# MRCS-Don-Wood-IR-Detector-Circuit.net
KiCad netlist of a schematic drawn in EAGLE
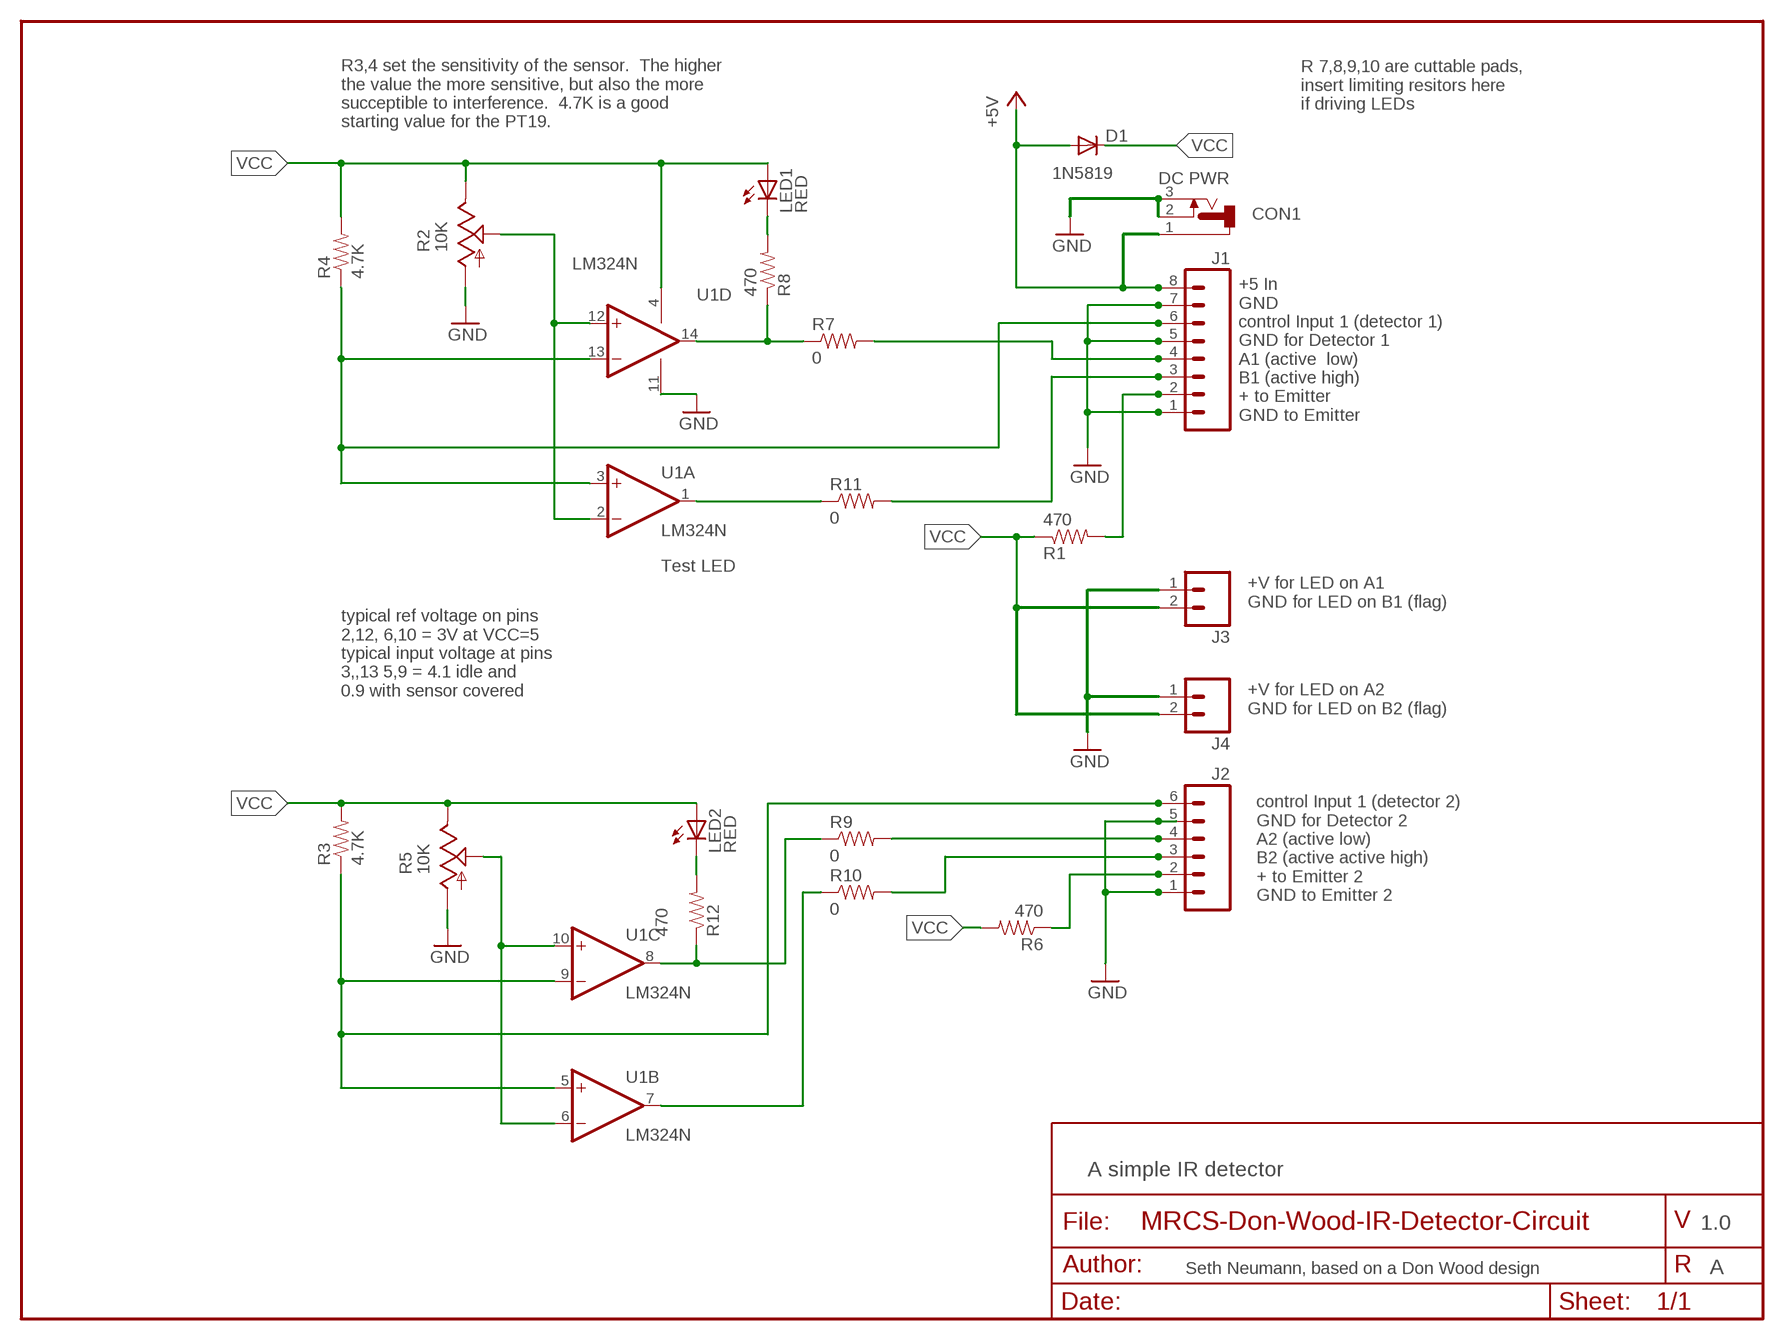
[diagram p0: schematic, sheet 1]

(export (version "E")
  (design (tool "Eeschema 10.0.6"))
  (components
    (comp (ref "CON1")
      (value "DC PWR")
      (footprint "eagle-import:DCJ0202")
      (libsource (lib "eagle-import") (part "CONNECTOR-DC-POWER-RA"))
    )
    (comp (ref "D1")
      (value "1N5819")
      (footprint "eagle-import:DIODE-1N4001")
      (libsource (lib "eagle-import") (part "DIODEPTH"))
    )
    (comp (ref "J1")
      (value "CONNECTOR-M08LOCK")
      (footprint "eagle-import:1X08_LOCK")
      (libsource (lib "eagle-import") (part "CONNECTOR-M08LOCK"))
    )
    (comp (ref "J2")
      (value "CONNECTOR-M06LOCK")
      (footprint "eagle-import:1X06_LOCK")
      (libsource (lib "eagle-import") (part "CONNECTOR-M06LOCK"))
    )
    (comp (ref "J3")
      (value "CONNECTOR-M021X02-LOCK")
      (footprint "eagle-import:1X02_LOCK")
      (libsource (lib "eagle-import") (part "CONNECTOR-M021X02-LOCK"))
    )
    (comp (ref "J4")
      (value "CONNECTOR-M021X02-LOCK")
      (footprint "eagle-import:1X02_LOCK")
      (libsource (lib "eagle-import") (part "CONNECTOR-M021X02-LOCK"))
    )
    (comp (ref "LED1")
      (value "RED")
      (footprint "eagle-import:LED3MM")
      (libsource (lib "eagle-import") (part "LEDLED3MM"))
    )
    (comp (ref "LED2")
      (value "RED")
      (footprint "eagle-import:LED3MM")
      (libsource (lib "eagle-import") (part "LEDLED3MM"))
    )
    (comp (ref "R1")
      (value "470")
      (footprint "eagle-import:AXIAL-0.4-RES")
      (libsource (lib "eagle-import") (part "RPTH04"))
    )
    (comp (ref "R2")
      (value "10K")
      (footprint "eagle-import:RS3")
      (libsource (lib "eagle-import") (part "TRIM_US-RS3"))
    )
    (comp (ref "R3")
      (value "4.7K")
      (footprint "eagle-import:AXIAL-0.4-RES")
      (libsource (lib "eagle-import") (part "RPTH04"))
    )
    (comp (ref "R4")
      (value "4.7K")
      (footprint "eagle-import:AXIAL-0.4-RES")
      (libsource (lib "eagle-import") (part "RPTH04"))
    )
    (comp (ref "R5")
      (value "10K")
      (footprint "eagle-import:RS3")
      (libsource (lib "eagle-import") (part "TRIM_US-RS3"))
    )
    (comp (ref "R6")
      (value "470")
      (footprint "eagle-import:AXIAL-0.4-RES")
      (libsource (lib "eagle-import") (part "RPTH04"))
    )
    (comp (ref "R7")
      (value "0")
      (footprint "eagle-import:CUT-R")
      (libsource (lib "eagle-import") (part "RPTH-R0"))
    )
    (comp (ref "R8")
      (value "470")
      (footprint "eagle-import:AXIAL-0.4-RES")
      (libsource (lib "eagle-import") (part "RPTH04"))
    )
    (comp (ref "R9")
      (value "0")
      (footprint "eagle-import:CUT-R")
      (libsource (lib "eagle-import") (part "RPTH-R0"))
    )
    (comp (ref "R10")
      (value "0")
      (footprint "eagle-import:CUT-R")
      (libsource (lib "eagle-import") (part "RPTH-R0"))
    )
    (comp (ref "R11")
      (value "0")
      (footprint "eagle-import:CUT-R")
      (libsource (lib "eagle-import") (part "RPTH-R0"))
    )
    (comp (ref "R12")
      (value "470")
      (footprint "eagle-import:AXIAL-0.4-RES")
      (libsource (lib "eagle-import") (part "RPTH04"))
    )
    (comp (ref "U1")
      (value "LM324N")
      (footprint "eagle-import:DIL14")
      (libsource (lib "eagle-import") (part "LM324N"))
    )
  )
  (nets
    (net (code "1") (name "+5V") (class "Default")
      (node (ref "CON1") (pin "1") (pinfunction "1_1") (pintype "passive"))
      (node (ref "D1") (pin "A") (pinfunction "A_A") (pintype "passive"))
      (node (ref "J1") (pin "8") (pinfunction "8_8") (pintype "passive"))
    )
    (net (code "2") (name "GND") (class "Default")
      (node (ref "CON1") (pin "2") (pinfunction "2_2") (pintype "passive"))
      (node (ref "CON1") (pin "3") (pinfunction "3_3") (pintype "passive"))
      (node (ref "J1") (pin "1") (pinfunction "1_1") (pintype "passive"))
      (node (ref "J1") (pin "5") (pinfunction "5_5") (pintype "passive"))
      (node (ref "J1") (pin "7") (pinfunction "7_7") (pintype "passive"))
      (node (ref "J2") (pin "1") (pinfunction "1_1") (pintype "passive"))
      (node (ref "J2") (pin "5") (pinfunction "5_5") (pintype "passive"))
      (node (ref "J3") (pin "1") (pinfunction "A_1") (pintype "passive"))
      (node (ref "J4") (pin "1") (pinfunction "A_1") (pintype "passive"))
      (node (ref "R2") (pin "A") (pinfunction "A_A") (pintype "passive"))
      (node (ref "R5") (pin "A") (pinfunction "A_A") (pintype "passive"))
      (node (ref "U1") (pin "11") (pinfunction "V-_11") (pintype "power_in"))
    )
    (net (code "3") (name "Net-(LED1-C)") (class "Default")
      (node (ref "LED1") (pin "K") (pinfunction "C_K") (pintype "passive"))
      (node (ref "R8") (pin "P$2") (pinfunction "2_P$2") (pintype "passive"))
    )
    (net (code "4") (name "Net-(LED2-C)") (class "Default")
      (node (ref "LED2") (pin "K") (pinfunction "C_K") (pintype "passive"))
      (node (ref "R12") (pin "P$2") (pinfunction "2_P$2") (pintype "passive"))
    )
    (net (code "5") (name "Net-(R1-2)") (class "Default")
      (node (ref "J1") (pin "2") (pinfunction "2_2") (pintype "passive"))
      (node (ref "R1") (pin "P$2") (pinfunction "2_P$2") (pintype "passive"))
    )
    (net (code "6") (name "Net-(R3-1)") (class "Default")
      (node (ref "J2") (pin "6") (pinfunction "6_6") (pintype "passive"))
      (node (ref "R3") (pin "P$1") (pinfunction "1_P$1") (pintype "passive"))
      (node (ref "U1") (pin "5") (pinfunction "+IN_5") (pintype "input"))
      (node (ref "U1") (pin "9") (pinfunction "-IN_9") (pintype "input"))
    )
    (net (code "7") (name "Net-(R4-1)") (class "Default")
      (node (ref "J1") (pin "6") (pinfunction "6_6") (pintype "passive"))
      (node (ref "R4") (pin "P$1") (pinfunction "1_P$1") (pintype "passive"))
      (node (ref "U1") (pin "13") (pinfunction "-IN_13") (pintype "input"))
      (node (ref "U1") (pin "3") (pinfunction "+IN_3") (pintype "input"))
    )
    (net (code "8") (name "Net-(R6-1)") (class "Default")
      (node (ref "J2") (pin "2") (pinfunction "2_2") (pintype "passive"))
      (node (ref "R6") (pin "P$1") (pinfunction "1_P$1") (pintype "passive"))
    )
    (net (code "9") (name "Net-(R7-1)") (class "Default")
      (node (ref "R7") (pin "P2") (pinfunction "1_P2") (pintype "passive"))
      (node (ref "R8") (pin "P$1") (pinfunction "1_P$1") (pintype "passive"))
      (node (ref "U1") (pin "14") (pinfunction "OUT_14") (pintype "output"))
    )
    (net (code "10") (name "Net-(R7-2)") (class "Default")
      (node (ref "J1") (pin "4") (pinfunction "4_4") (pintype "passive"))
      (node (ref "R7") (pin "P1") (pinfunction "2_P1") (pintype "passive"))
    )
    (net (code "11") (name "Net-(R9-2)") (class "Default")
      (node (ref "J2") (pin "4") (pinfunction "4_4") (pintype "passive"))
      (node (ref "R9") (pin "P1") (pinfunction "2_P1") (pintype "passive"))
    )
    (net (code "12") (name "Net-(R10-1)") (class "Default")
      (node (ref "R10") (pin "P2") (pinfunction "1_P2") (pintype "passive"))
      (node (ref "U1") (pin "7") (pinfunction "OUT_7") (pintype "output"))
    )
    (net (code "13") (name "Net-(R10-2)") (class "Default")
      (node (ref "J2") (pin "3") (pinfunction "3_3") (pintype "passive"))
      (node (ref "R10") (pin "P1") (pinfunction "2_P1") (pintype "passive"))
    )
    (net (code "14") (name "Net-(R11-1)") (class "Default")
      (node (ref "R11") (pin "P2") (pinfunction "1_P2") (pintype "passive"))
      (node (ref "U1") (pin "1") (pinfunction "OUT_1") (pintype "output"))
    )
    (net (code "15") (name "Net-(R11-2)") (class "Default")
      (node (ref "J1") (pin "3") (pinfunction "3_3") (pintype "passive"))
      (node (ref "R11") (pin "P1") (pinfunction "2_P1") (pintype "passive"))
    )
    (net (code "16") (name "Net-(R12-1)") (class "Default")
      (node (ref "R12") (pin "P$1") (pinfunction "1_P$1") (pintype "passive"))
      (node (ref "R9") (pin "P2") (pinfunction "1_P2") (pintype "passive"))
      (node (ref "U1") (pin "8") (pinfunction "OUT_8") (pintype "output"))
    )
    (net (code "17") (name "Net-(U1A--IN)") (class "Default")
      (node (ref "R2") (pin "S") (pinfunction "S_S") (pintype "passive"))
      (node (ref "U1") (pin "12") (pinfunction "+IN_12") (pintype "input"))
      (node (ref "U1") (pin "2") (pinfunction "-IN_2") (pintype "input"))
    )
    (net (code "18") (name "Net-(U1B--IN)") (class "Default")
      (node (ref "R5") (pin "S") (pinfunction "S_S") (pintype "passive"))
      (node (ref "U1") (pin "10") (pinfunction "+IN_10") (pintype "input"))
      (node (ref "U1") (pin "6") (pinfunction "-IN_6") (pintype "input"))
    )
    (net (code "19") (name "VCC") (class "Default")
      (node (ref "D1") (pin "C") (pinfunction "C_C") (pintype "passive"))
      (node (ref "J3") (pin "2") (pinfunction "B_2") (pintype "passive"))
      (node (ref "J4") (pin "2") (pinfunction "B_2") (pintype "passive"))
      (node (ref "LED1") (pin "A") (pinfunction "A_A") (pintype "passive"))
      (node (ref "LED2") (pin "A") (pinfunction "A_A") (pintype "passive"))
      (node (ref "R1") (pin "P$1") (pinfunction "1_P$1") (pintype "passive"))
      (node (ref "R2") (pin "E") (pinfunction "E_E") (pintype "passive"))
      (node (ref "R3") (pin "P$2") (pinfunction "2_P$2") (pintype "passive"))
      (node (ref "R4") (pin "P$2") (pinfunction "2_P$2") (pintype "passive"))
      (node (ref "R5") (pin "E") (pinfunction "E_E") (pintype "passive"))
      (node (ref "R6") (pin "P$2") (pinfunction "2_P$2") (pintype "passive"))
      (node (ref "U1") (pin "4") (pinfunction "V+_4") (pintype "power_in"))
    )
  )
)
